# motor_board.net
KiCad netlist of a schematic drawn in EAGLE
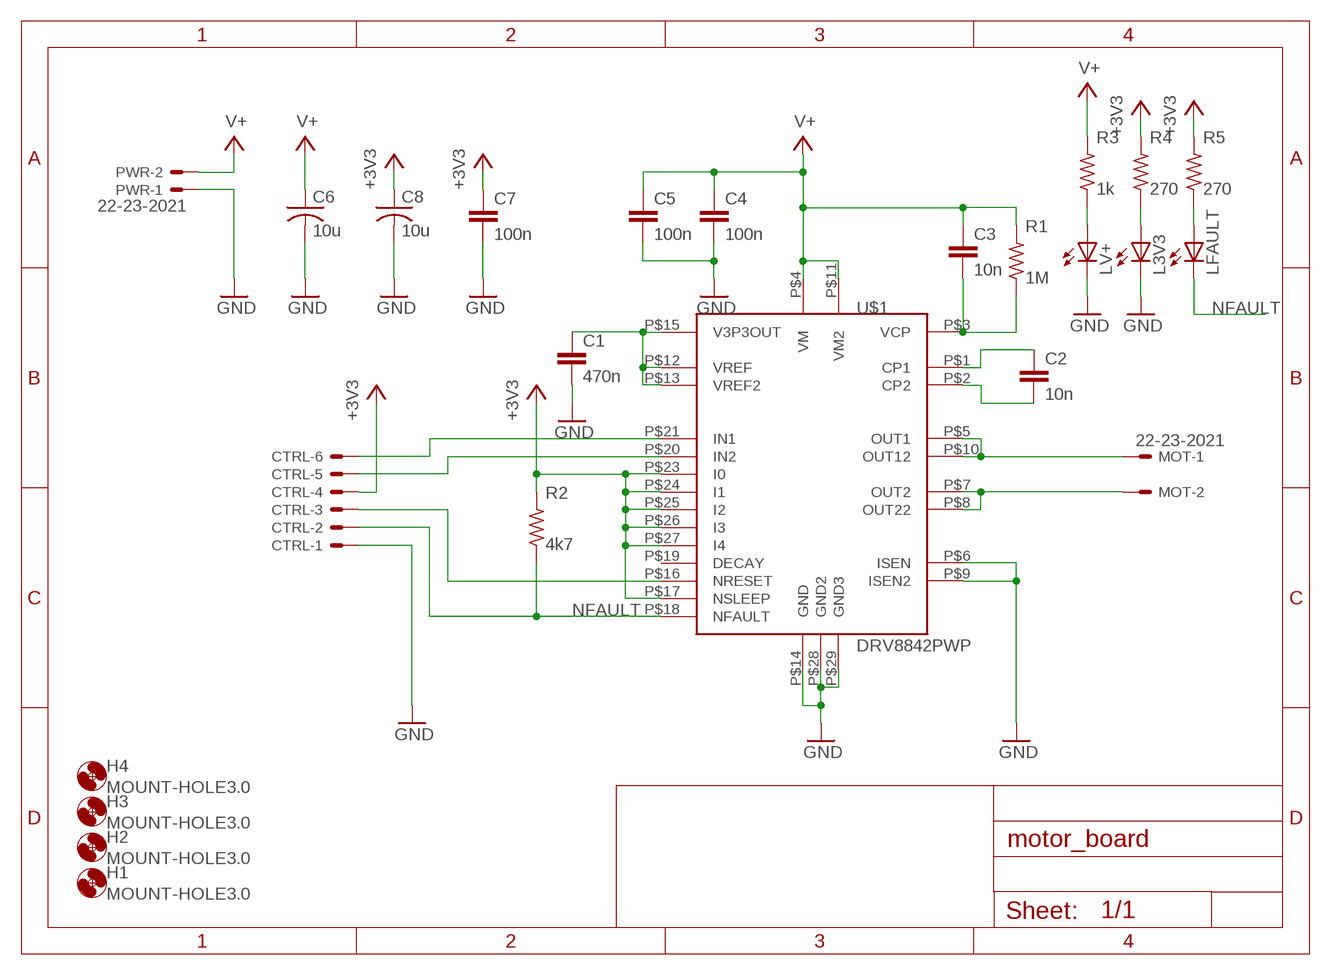
[diagram p0: schematic, sheet 1]

(export (version "E")
  (design (tool "Eeschema 10.0.6"))
  (components
    (comp (ref "C1")
      (value "470n")
      (footprint "eagle-import:C0603K")
      (libsource (lib "eagle-import") (part "C-EUC0603K"))
    )
    (comp (ref "C2")
      (value "10n")
      (footprint "eagle-import:C0603K")
      (libsource (lib "eagle-import") (part "C-EUC0603K"))
    )
    (comp (ref "C3")
      (value "10n")
      (footprint "eagle-import:C0603K")
      (libsource (lib "eagle-import") (part "C-EUC0603K"))
    )
    (comp (ref "C4")
      (value "100n")
      (footprint "eagle-import:C0603K")
      (libsource (lib "eagle-import") (part "C-EUC0603K"))
    )
    (comp (ref "C5")
      (value "100n")
      (footprint "eagle-import:C0603K")
      (libsource (lib "eagle-import") (part "C-EUC0603K"))
    )
    (comp (ref "C6")
      (value "10u")
      (footprint "eagle-import:C0805K")
      (libsource (lib "eagle-import") (part "C-USC0805K"))
    )
    (comp (ref "C7")
      (value "100n")
      (footprint "eagle-import:C0603K")
      (libsource (lib "eagle-import") (part "C-EUC0603K"))
    )
    (comp (ref "C8")
      (value "10u")
      (footprint "eagle-import:C0805K")
      (libsource (lib "eagle-import") (part "C-USC0805K"))
    )
    (comp (ref "CTRL")
      (value "22-23-2061")
      (footprint "eagle-import:22-23-2061")
      (fields (field (name "MF") "MOLEX"))
      (libsource (lib "eagle-import") (part "22-23-2061"))
    )
    (comp (ref "H1")
      (value "MOUNT-HOLE3.0")
      (footprint "eagle-import:3,0")
      (libsource (lib "eagle-import") (part "MOUNT-HOLE3.0"))
    )
    (comp (ref "H2")
      (value "MOUNT-HOLE3.0")
      (footprint "eagle-import:3,0")
      (libsource (lib "eagle-import") (part "MOUNT-HOLE3.0"))
    )
    (comp (ref "H3")
      (value "MOUNT-HOLE3.0")
      (footprint "eagle-import:3,0")
      (libsource (lib "eagle-import") (part "MOUNT-HOLE3.0"))
    )
    (comp (ref "H4")
      (value "MOUNT-HOLE3.0")
      (footprint "eagle-import:3,0")
      (libsource (lib "eagle-import") (part "MOUNT-HOLE3.0"))
    )
    (comp (ref "L3V3")
      (value "LEDCHIPLED_0603")
      (footprint "eagle-import:CHIPLED_0603")
      (libsource (lib "eagle-import") (part "LEDCHIPLED_0603"))
    )
    (comp (ref "LFAULT")
      (value "LEDCHIPLED_0603")
      (footprint "eagle-import:CHIPLED_0603")
      (libsource (lib "eagle-import") (part "LEDCHIPLED_0603"))
    )
    (comp (ref "LV+")
      (value "LEDCHIPLED_0603")
      (footprint "eagle-import:CHIPLED_0603")
      (libsource (lib "eagle-import") (part "LEDCHIPLED_0603"))
    )
    (comp (ref "MOT")
      (value "22-23-2021")
      (footprint "eagle-import:22-23-2021")
      (fields (field (name "MF") "MOLEX"))
      (libsource (lib "eagle-import") (part "22-23-2021"))
    )
    (comp (ref "PWR")
      (value "22-23-2021")
      (footprint "eagle-import:22-23-2021")
      (fields (field (name "MF") "MOLEX"))
      (libsource (lib "eagle-import") (part "22-23-2021"))
    )
    (comp (ref "R1")
      (value "1M")
      (footprint "eagle-import:R0603")
      (libsource (lib "eagle-import") (part "R-US_R0603"))
    )
    (comp (ref "R2")
      (value "4k7")
      (footprint "eagle-import:R0603")
      (libsource (lib "eagle-import") (part "R-US_R0603"))
    )
    (comp (ref "R3")
      (value "1k")
      (footprint "eagle-import:R0603")
      (libsource (lib "eagle-import") (part "R-US_R0603"))
    )
    (comp (ref "R4")
      (value "270")
      (footprint "eagle-import:R0603")
      (libsource (lib "eagle-import") (part "R-US_R0603"))
    )
    (comp (ref "R5")
      (value "270")
      (footprint "eagle-import:R0603")
      (libsource (lib "eagle-import") (part "R-US_R0603"))
    )
    (comp (ref "U$1")
      (value "DRV8842PWP")
      (footprint "eagle-import:R-PDS0-G28")
      (libsource (lib "eagle-import") (part "DRV8842PWP"))
    )
  )
  (nets
    (net (code "1") (name "+3V3") (class "Default")
      (node (ref "C7") (pin "1") (pinfunction "1_1") (pintype "passive"))
      (node (ref "C8") (pin "1") (pinfunction "1_1") (pintype "passive"))
      (node (ref "CTRL") (pin "4") (pinfunction "S_4") (pintype "passive"))
      (node (ref "R2") (pin "2") (pinfunction "2_2") (pintype "passive"))
      (node (ref "R4") (pin "2") (pinfunction "2_2") (pintype "passive"))
      (node (ref "R5") (pin "2") (pinfunction "2_2") (pintype "passive"))
      (node (ref "U$1") (pin "P$17") (pinfunction "NSLEEP_P$17") (pintype "bidirectional"))
      (node (ref "U$1") (pin "P$23") (pinfunction "I0_P$23") (pintype "bidirectional"))
      (node (ref "U$1") (pin "P$24") (pinfunction "I1_P$24") (pintype "bidirectional"))
      (node (ref "U$1") (pin "P$25") (pinfunction "I2_P$25") (pintype "bidirectional"))
      (node (ref "U$1") (pin "P$26") (pinfunction "I3_P$26") (pintype "bidirectional"))
      (node (ref "U$1") (pin "P$27") (pinfunction "I4_P$27") (pintype "bidirectional"))
    )
    (net (code "2") (name "/NFAULT") (class "Default")
      (node (ref "CTRL") (pin "2") (pinfunction "S_2") (pintype "passive"))
      (node (ref "LFAULT") (pin "C") (pinfunction "C_C") (pintype "passive"))
      (node (ref "R2") (pin "1") (pinfunction "1_1") (pintype "passive"))
      (node (ref "U$1") (pin "P$18") (pinfunction "NFAULT_P$18") (pintype "bidirectional"))
    )
    (net (code "3") (name "GND") (class "Default")
      (node (ref "C1") (pin "2") (pinfunction "2_2") (pintype "passive"))
      (node (ref "C4") (pin "2") (pinfunction "2_2") (pintype "passive"))
      (node (ref "C5") (pin "2") (pinfunction "2_2") (pintype "passive"))
      (node (ref "C6") (pin "2") (pinfunction "2_2") (pintype "passive"))
      (node (ref "C7") (pin "2") (pinfunction "2_2") (pintype "passive"))
      (node (ref "C8") (pin "2") (pinfunction "2_2") (pintype "passive"))
      (node (ref "CTRL") (pin "1") (pinfunction "S_1") (pintype "passive"))
      (node (ref "L3V3") (pin "C") (pinfunction "C_C") (pintype "passive"))
      (node (ref "LV+") (pin "C") (pinfunction "C_C") (pintype "passive"))
      (node (ref "PWR") (pin "1") (pinfunction "S_1") (pintype "passive"))
      (node (ref "U$1") (pin "P$14") (pinfunction "GND_P$14") (pintype "bidirectional"))
      (node (ref "U$1") (pin "P$28") (pinfunction "GND2_P$28") (pintype "bidirectional"))
      (node (ref "U$1") (pin "P$29") (pinfunction "GND3_P$29") (pintype "bidirectional"))
      (node (ref "U$1") (pin "P$6") (pinfunction "ISEN_P$6") (pintype "bidirectional"))
      (node (ref "U$1") (pin "P$9") (pinfunction "ISEN2_P$9") (pintype "bidirectional"))
    )
    (net (code "4") (name "Net-(CTRLC-S)") (class "Default")
      (node (ref "CTRL") (pin "3") (pinfunction "S_3") (pintype "passive"))
      (node (ref "U$1") (pin "P$16") (pinfunction "NRESET_P$16") (pintype "bidirectional"))
    )
    (net (code "5") (name "Net-(CTRLE-S)") (class "Default")
      (node (ref "CTRL") (pin "5") (pinfunction "S_5") (pintype "passive"))
      (node (ref "U$1") (pin "P$20") (pinfunction "IN2_P$20") (pintype "bidirectional"))
    )
    (net (code "6") (name "Net-(CTRLF-S)") (class "Default")
      (node (ref "CTRL") (pin "6") (pinfunction "S_6") (pintype "passive"))
      (node (ref "U$1") (pin "P$21") (pinfunction "IN1_P$21") (pintype "bidirectional"))
    )
    (net (code "7") (name "Net-(L3V3-PadA)") (class "Default")
      (node (ref "L3V3") (pin "A") (pinfunction "A_A") (pintype "passive"))
      (node (ref "R4") (pin "1") (pinfunction "1_1") (pintype "passive"))
    )
    (net (code "8") (name "Net-(LFAULT-PadA)") (class "Default")
      (node (ref "LFAULT") (pin "A") (pinfunction "A_A") (pintype "passive"))
      (node (ref "R5") (pin "1") (pinfunction "1_1") (pintype "passive"))
    )
    (net (code "9") (name "Net-(LV+-PadA)") (class "Default")
      (node (ref "LV+") (pin "A") (pinfunction "A_A") (pintype "passive"))
      (node (ref "R3") (pin "1") (pinfunction "1_1") (pintype "passive"))
    )
    (net (code "10") (name "Net-(MOTA-S)") (class "Default")
      (node (ref "MOT") (pin "1") (pinfunction "S_1") (pintype "passive"))
      (node (ref "U$1") (pin "P$10") (pinfunction "OUT12_P$10") (pintype "bidirectional"))
      (node (ref "U$1") (pin "P$5") (pinfunction "OUT1_P$5") (pintype "bidirectional"))
    )
    (net (code "11") (name "Net-(MOTB-S)") (class "Default")
      (node (ref "MOT") (pin "2") (pinfunction "S_2") (pintype "passive"))
      (node (ref "U$1") (pin "P$7") (pinfunction "OUT2_P$7") (pintype "bidirectional"))
      (node (ref "U$1") (pin "P$8") (pinfunction "OUT22_P$8") (pintype "bidirectional"))
    )
    (net (code "12") (name "Net-(U$1-CP1)") (class "Default")
      (node (ref "C2") (pin "1") (pinfunction "1_1") (pintype "passive"))
      (node (ref "U$1") (pin "P$1") (pinfunction "CP1_P$1") (pintype "bidirectional"))
    )
    (net (code "13") (name "Net-(U$1-CP2)") (class "Default")
      (node (ref "C2") (pin "2") (pinfunction "2_2") (pintype "passive"))
      (node (ref "U$1") (pin "P$2") (pinfunction "CP2_P$2") (pintype "bidirectional"))
    )
    (net (code "14") (name "Net-(U$1-V3P3OUT)") (class "Default")
      (node (ref "C1") (pin "1") (pinfunction "1_1") (pintype "passive"))
      (node (ref "U$1") (pin "P$12") (pinfunction "VREF_P$12") (pintype "bidirectional"))
      (node (ref "U$1") (pin "P$13") (pinfunction "VREF2_P$13") (pintype "bidirectional"))
      (node (ref "U$1") (pin "P$15") (pinfunction "V3P3OUT_P$15") (pintype "bidirectional"))
    )
    (net (code "15") (name "Net-(U$1-VCP)") (class "Default")
      (node (ref "C3") (pin "2") (pinfunction "2_2") (pintype "passive"))
      (node (ref "R1") (pin "1") (pinfunction "1_1") (pintype "passive"))
      (node (ref "U$1") (pin "P$3") (pinfunction "VCP_P$3") (pintype "bidirectional"))
    )
    (net (code "16") (name "V+") (class "Default")
      (node (ref "C3") (pin "1") (pinfunction "1_1") (pintype "passive"))
      (node (ref "C4") (pin "1") (pinfunction "1_1") (pintype "passive"))
      (node (ref "C5") (pin "1") (pinfunction "1_1") (pintype "passive"))
      (node (ref "C6") (pin "1") (pinfunction "1_1") (pintype "passive"))
      (node (ref "PWR") (pin "2") (pinfunction "S_2") (pintype "passive"))
      (node (ref "R1") (pin "2") (pinfunction "2_2") (pintype "passive"))
      (node (ref "R3") (pin "2") (pinfunction "2_2") (pintype "passive"))
      (node (ref "U$1") (pin "P$11") (pinfunction "VM2_P$11") (pintype "bidirectional"))
      (node (ref "U$1") (pin "P$4") (pinfunction "VM_P$4") (pintype "bidirectional"))
    )
    (net (code "17") (name "unconnected-(U$1-DECAY-PadP$19)") (class "Default")
      (node (ref "U$1") (pin "P$19") (pinfunction "DECAY_P$19") (pintype "bidirectional"))
    )
  )
)
